# Sheet1.net
KiCad netlist of a schematic drawn in Altium Designer
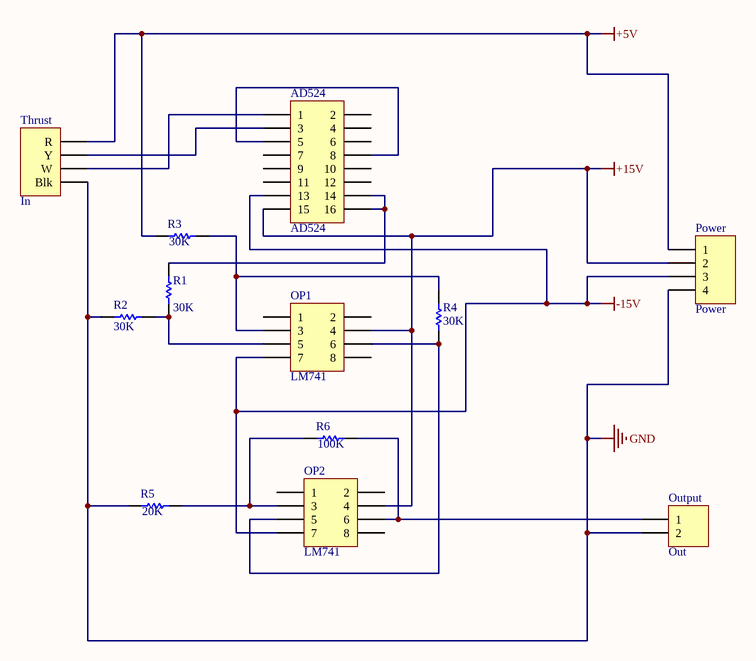
[diagram p0: Sheet1.SchDoc]

(export (version "E")
  (design (tool "Eeschema 10.0.6"))
  (components
    (comp (ref "AD524")
      (value "AD524")
      (footprint "HDR2X8")
      (description "Header, 8-Pin, Dual row")
      (fields (field (name "PUBLISHER") "Altium Limited"))
      (libsource (lib "Miscellaneous Connectors") (part "Header 8X2"))
    )
    (comp (ref "OP1")
      (value "LM741")
      (footprint "HDR2X4")
      (description "Header, 4-Pin, Dual row")
      (fields (field (name "PUBLISHER") "Altium Limited"))
      (libsource (lib "Miscellaneous Connectors") (part "Header 4X2"))
    )
    (comp (ref "OP2")
      (value "LM741")
      (footprint "HDR2X4")
      (description "Header, 4-Pin, Dual row")
      (fields (field (name "PUBLISHER") "Altium Limited"))
      (libsource (lib "Miscellaneous Connectors") (part "Header 4X2"))
    )
    (comp (ref "Output")
      (value "Out")
      (footprint "HDR1X2")
      (description "Header, 2-Pin")
      (fields (field (name "PUBLISHER") "Altium Limited"))
      (libsource (lib "Miscellaneous Connectors") (part "Header 2"))
    )
    (comp (ref "Power")
      (value "Power")
      (footprint "HDR1X4")
      (description "Header, 4-Pin")
      (fields (field (name "PUBLISHER") "Altium Limited"))
      (libsource (lib "Miscellaneous Connectors") (part "Header 4"))
    )
    (comp (ref "R1")
      (value "30K")
      (footprint "AXIAL-0.3")
      (description "Resistor")
      (fields (field (name "Comment") "Res1") (field (name "PUBLISHER") "Altium Limited"))
      (libsource (lib "Miscellaneous Devices") (part "Res1"))
    )
    (comp (ref "R2")
      (value "30K")
      (footprint "AXIAL-0.3")
      (description "Resistor")
      (fields (field (name "Comment") "Res2") (field (name "PUBLISHER") "Altium Limited"))
      (libsource (lib "Miscellaneous Devices") (part "Res1"))
    )
    (comp (ref "R3")
      (value "30K")
      (footprint "AXIAL-0.3")
      (description "Resistor")
      (fields (field (name "Comment") "Res3") (field (name "PUBLISHER") "Altium Limited"))
      (libsource (lib "Miscellaneous Devices") (part "Res1"))
    )
    (comp (ref "R4")
      (value "30K")
      (footprint "AXIAL-0.3")
      (description "Resistor")
      (fields (field (name "Comment") "Res4") (field (name "PUBLISHER") "Altium Limited"))
      (libsource (lib "Miscellaneous Devices") (part "Res1"))
    )
    (comp (ref "R5")
      (value "20K")
      (footprint "AXIAL-0.3")
      (description "Resistor")
      (fields (field (name "Comment") "Res5") (field (name "PUBLISHER") "Altium Limited"))
      (libsource (lib "Miscellaneous Devices") (part "Res1"))
    )
    (comp (ref "R6")
      (value "100K")
      (footprint "AXIAL-0.3")
      (description "Resistor")
      (fields (field (name "Comment") "Res6") (field (name "PUBLISHER") "Altium Limited"))
      (libsource (lib "Miscellaneous Devices") (part "Res1"))
    )
    (comp (ref "Thrust")
      (value "In")
      (footprint "HDR1X4")
      (description "Header, 4-Pin")
      (fields (field (name "PUBLISHER") "Altium Limited"))
      (libsource (lib "") (part "Header 4_1"))
    )
  )
  (nets
    (net (code "1") (name "+5V") (class "Default")
      (node (ref "Power") (pin "1") (pinfunction "1_1") (pintype "passive"))
      (node (ref "R3") (pin "1") (pinfunction "1_1") (pintype "passive"))
      (node (ref "Thrust") (pin "1") (pinfunction "R_1") (pintype "passive"))
    )
    (net (code "2") (name "+15V") (class "Default")
      (node (ref "AD524") (pin "15") (pinfunction "15_15") (pintype "passive"))
      (node (ref "OP1") (pin "4") (pinfunction "4_4") (pintype "passive"))
      (node (ref "OP2") (pin "4") (pinfunction "4_4") (pintype "passive"))
      (node (ref "Power") (pin "2") (pinfunction "2_2") (pintype "passive"))
    )
    (net (code "3") (name "-15V") (class "Default")
      (node (ref "AD524") (pin "13") (pinfunction "13_13") (pintype "passive"))
      (node (ref "OP1") (pin "7") (pinfunction "7_7") (pintype "passive"))
      (node (ref "OP2") (pin "7") (pinfunction "7_7") (pintype "passive"))
      (node (ref "Power") (pin "3") (pinfunction "3_3") (pintype "passive"))
    )
    (net (code "4") (name "GND") (class "Default")
      (node (ref "Output") (pin "2") (pinfunction "2_2") (pintype "passive"))
      (node (ref "Power") (pin "4") (pinfunction "4_4") (pintype "passive"))
      (node (ref "R2") (pin "2") (pinfunction "2_2") (pintype "passive"))
      (node (ref "R5") (pin "1") (pinfunction "1_1") (pintype "passive"))
      (node (ref "Thrust") (pin "4") (pinfunction "Blk_4") (pintype "passive"))
    )
    (net (code "5") (name "Net-(AD524-Pad5)") (class "Default")
      (node (ref "AD524") (pin "5") (pinfunction "5_5") (pintype "passive"))
      (node (ref "AD524") (pin "8") (pinfunction "8_8") (pintype "passive"))
    )
    (net (code "6") (name "Net-(AD524-Pad14)") (class "Default")
      (node (ref "AD524") (pin "14") (pinfunction "14_14") (pintype "passive"))
      (node (ref "AD524") (pin "16") (pinfunction "16_16") (pintype "passive"))
      (node (ref "R1") (pin "2") (pinfunction "2_2") (pintype "passive"))
    )
    (net (code "7") (name "Net-(OP1-Pad3)") (class "Default")
      (node (ref "OP1") (pin "3") (pinfunction "3_3") (pintype "passive"))
      (node (ref "R3") (pin "2") (pinfunction "2_2") (pintype "passive"))
      (node (ref "R4") (pin "2") (pinfunction "2_2") (pintype "passive"))
    )
    (net (code "8") (name "Net-(OP1-Pad5)") (class "Default")
      (node (ref "OP1") (pin "5") (pinfunction "5_5") (pintype "passive"))
      (node (ref "R1") (pin "1") (pinfunction "1_1") (pintype "passive"))
      (node (ref "R2") (pin "1") (pinfunction "1_1") (pintype "passive"))
    )
    (net (code "9") (name "Net-(OP1-Pad6)") (class "Default")
      (node (ref "OP1") (pin "6") (pinfunction "6_6") (pintype "passive"))
      (node (ref "OP2") (pin "5") (pinfunction "5_5") (pintype "passive"))
      (node (ref "R4") (pin "1") (pinfunction "1_1") (pintype "passive"))
    )
    (net (code "10") (name "Net-(OP2-Pad3)") (class "Default")
      (node (ref "OP2") (pin "3") (pinfunction "3_3") (pintype "passive"))
      (node (ref "R5") (pin "2") (pinfunction "2_2") (pintype "passive"))
      (node (ref "R6") (pin "1") (pinfunction "1_1") (pintype "passive"))
    )
    (net (code "11") (name "Net-(OP2-Pad6)") (class "Default")
      (node (ref "OP2") (pin "6") (pinfunction "6_6") (pintype "passive"))
      (node (ref "Output") (pin "1") (pinfunction "1_1") (pintype "passive"))
      (node (ref "R6") (pin "2") (pinfunction "2_2") (pintype "passive"))
    )
    (net (code "12") (name "Net-(Thrust-W)") (class "Default")
      (node (ref "AD524") (pin "1") (pinfunction "1_1") (pintype "passive"))
      (node (ref "Thrust") (pin "3") (pinfunction "W_3") (pintype "passive"))
    )
    (net (code "13") (name "Net-(Thrust-Y)") (class "Default")
      (node (ref "AD524") (pin "3") (pinfunction "3_3") (pintype "passive"))
      (node (ref "Thrust") (pin "2") (pinfunction "Y_2") (pintype "passive"))
    )
    (net (code "14") (name "unconnected-(AD524-Pad2)") (class "Default")
      (node (ref "AD524") (pin "2") (pinfunction "2_2") (pintype "passive"))
    )
    (net (code "15") (name "unconnected-(AD524-Pad4)") (class "Default")
      (node (ref "AD524") (pin "4") (pinfunction "4_4") (pintype "passive"))
    )
    (net (code "16") (name "unconnected-(AD524-Pad6)") (class "Default")
      (node (ref "AD524") (pin "6") (pinfunction "6_6") (pintype "passive"))
    )
    (net (code "17") (name "unconnected-(AD524-Pad7)") (class "Default")
      (node (ref "AD524") (pin "7") (pinfunction "7_7") (pintype "passive"))
    )
    (net (code "18") (name "unconnected-(AD524-Pad9)") (class "Default")
      (node (ref "AD524") (pin "9") (pinfunction "9_9") (pintype "passive"))
    )
    (net (code "19") (name "unconnected-(AD524-Pad10)") (class "Default")
      (node (ref "AD524") (pin "10") (pinfunction "10_10") (pintype "passive"))
    )
    (net (code "20") (name "unconnected-(AD524-Pad11)") (class "Default")
      (node (ref "AD524") (pin "11") (pinfunction "11_11") (pintype "passive"))
    )
    (net (code "21") (name "unconnected-(AD524-Pad12)") (class "Default")
      (node (ref "AD524") (pin "12") (pinfunction "12_12") (pintype "passive"))
    )
    (net (code "22") (name "unconnected-(OP1-Pad1)") (class "Default")
      (node (ref "OP1") (pin "1") (pinfunction "1_1") (pintype "passive"))
    )
    (net (code "23") (name "unconnected-(OP1-Pad2)") (class "Default")
      (node (ref "OP1") (pin "2") (pinfunction "2_2") (pintype "passive"))
    )
    (net (code "24") (name "unconnected-(OP1-Pad8)") (class "Default")
      (node (ref "OP1") (pin "8") (pinfunction "8_8") (pintype "passive"))
    )
    (net (code "25") (name "unconnected-(OP2-Pad1)") (class "Default")
      (node (ref "OP2") (pin "1") (pinfunction "1_1") (pintype "passive"))
    )
    (net (code "26") (name "unconnected-(OP2-Pad2)") (class "Default")
      (node (ref "OP2") (pin "2") (pinfunction "2_2") (pintype "passive"))
    )
    (net (code "27") (name "unconnected-(OP2-Pad8)") (class "Default")
      (node (ref "OP2") (pin "8") (pinfunction "8_8") (pintype "passive"))
    )
  )
)
